# MCU009B_EmuInterface.net
KiCad netlist of a schematic drawn in Altium Designer
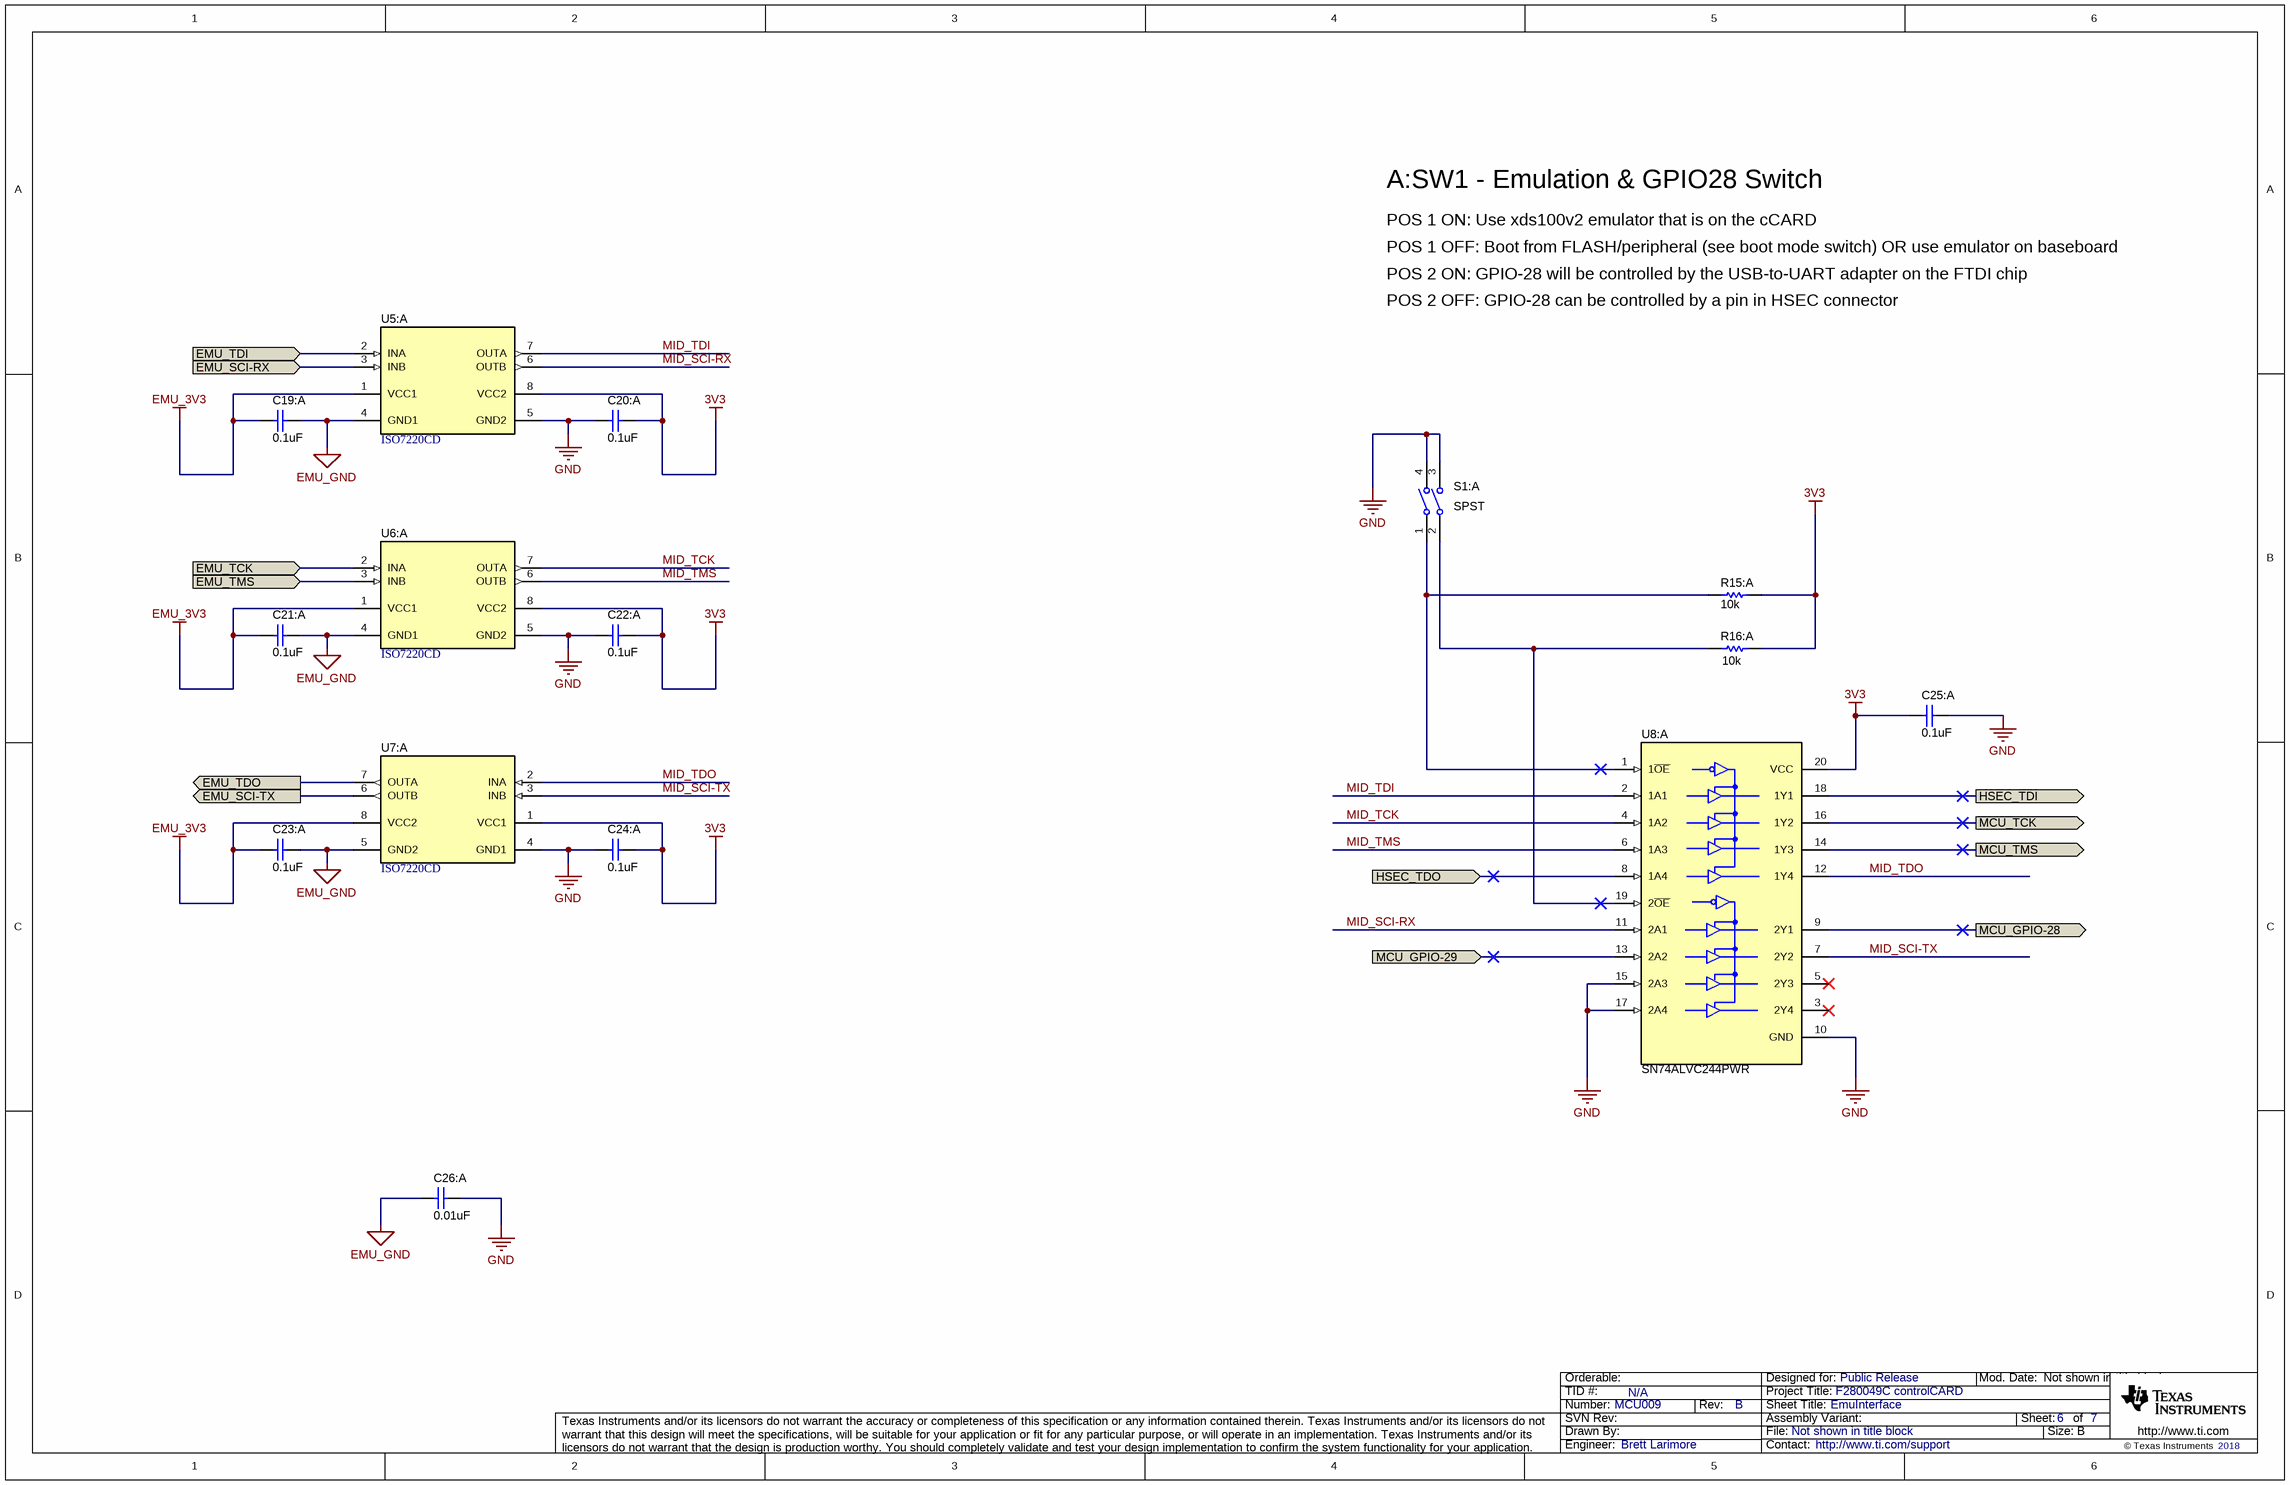
[diagram p0: MCU009B_EmuInterface.SchDoc]

(export (version "E")
  (design (tool "Eeschema 10.0.6"))
  (components
    (comp (ref "C19:A")
      (value "GRM155R71A104KA01D")
      (footprint "0402")
      (description "CAP, CERM, 0.1 uF, 10 V, +/- 10%, X7R, 0402")
      (fields
        (field (name "VALUEDISPLAYED") "0.1uF")
        (field (name "MANUFACTURER") "MuRata")
        (field (name "PUBLISHER") "Texas Instruments")
      )
      (libsource (lib "Altium Vault - TI") (part "Capacitor"))
    )
    (comp (ref "C20:A")
      (value "GRM155R71A104KA01D")
      (footprint "0402")
      (description "CAP, CERM, 0.1 uF, 10 V, +/- 10%, X7R, 0402")
      (fields
        (field (name "VALUEDISPLAYED") "0.1uF")
        (field (name "MANUFACTURER") "MuRata")
        (field (name "PUBLISHER") "Texas Instruments")
      )
      (libsource (lib "Altium Vault - TI") (part "Capacitor"))
    )
    (comp (ref "C21:A")
      (value "GRM155R71A104KA01D")
      (footprint "0402")
      (description "CAP, CERM, 0.1 uF, 10 V, +/- 10%, X7R, 0402")
      (fields
        (field (name "VALUEDISPLAYED") "0.1uF")
        (field (name "MANUFACTURER") "MuRata")
        (field (name "PUBLISHER") "Texas Instruments")
      )
      (libsource (lib "Altium Vault - TI") (part "Capacitor"))
    )
    (comp (ref "C22:A")
      (value "GRM155R71A104KA01D")
      (footprint "0402")
      (description "CAP, CERM, 0.1 uF, 10 V, +/- 10%, X7R, 0402")
      (fields
        (field (name "VALUEDISPLAYED") "0.1uF")
        (field (name "MANUFACTURER") "MuRata")
        (field (name "PUBLISHER") "Texas Instruments")
      )
      (libsource (lib "Altium Vault - TI") (part "Capacitor"))
    )
    (comp (ref "C23:A")
      (value "GRM155R71A104KA01D")
      (footprint "0402")
      (description "CAP, CERM, 0.1 uF, 10 V, +/- 10%, X7R, 0402")
      (fields
        (field (name "VALUEDISPLAYED") "0.1uF")
        (field (name "MANUFACTURER") "MuRata")
        (field (name "PUBLISHER") "Texas Instruments")
      )
      (libsource (lib "Altium Vault - TI") (part "Capacitor"))
    )
    (comp (ref "C24:A")
      (value "GRM155R71A104KA01D")
      (footprint "0402")
      (description "CAP, CERM, 0.1 uF, 10 V, +/- 10%, X7R, 0402")
      (fields
        (field (name "VALUEDISPLAYED") "0.1uF")
        (field (name "MANUFACTURER") "MuRata")
        (field (name "PUBLISHER") "Texas Instruments")
      )
      (libsource (lib "Altium Vault - TI") (part "Capacitor"))
    )
    (comp (ref "C25:A")
      (value "GRM155R71A104KA01D")
      (footprint "0402")
      (description "CAP, CERM, 0.1 uF, 10 V, +/- 10%, X7R, 0402")
      (fields
        (field (name "VALUEDISPLAYED") "0.1uF")
        (field (name "MANUFACTURER") "MuRata")
        (field (name "PUBLISHER") "Texas Instruments")
      )
      (libsource (lib "Altium Vault - TI") (part "Capacitor"))
    )
    (comp (ref "C26:A")
      (value "1812SC103KAT1A")
      (footprint "1812")
      (description "CAP, CERM, 0.01 uF, 1500 V, +/- 10%, X7R, 1812")
      (fields
        (field (name "VALUEDISPLAYED") "0.01uF")
        (field (name "MANUFACTURER") "AVX")
        (field (name "PUBLISHER") "Texas Instruments")
      )
      (libsource (lib "Altium Vault - TI") (part "Capacitor"))
    )
    (comp (ref "R15:A")
      (value "CRCW040210K0JNED")
      (footprint "0402")
      (description "RES, 10 k, 5%, 0.063 W, AEC-Q200 Grade 0, 0402")
      (fields (field (name "VALUEDISPLAYED") "10k") (field (name "MANUFACTURER") "Vishay-Dale"))
      (libsource (lib "Altium Vault - TI") (part "Resistor"))
    )
    (comp (ref "R16:A")
      (value "CRCW040210K0JNED")
      (footprint "0402")
      (description "RES, 10 k, 5%, 0.063 W, AEC-Q200 Grade 0, 0402")
      (fields (field (name "VALUEDISPLAYED") "10k") (field (name "MANUFACTURER") "Vishay-Dale"))
      (libsource (lib "Altium Vault - TI") (part "Resistor"))
    )
    (comp (ref "S1:A")
      (value "218-2LPST")
      (footprint "SW_218-2LP")
      (description "Switch, SPST, 2 Pos, 25mA, 24VDC, SMD")
      (fields
        (field (name "MANUFACTURER") "CTS Electrocomponents")
        (field (name "CIRCUIT") "SPST")
        (field (name "PUBLISHER") "Texas Instruments")
      )
      (libsource (lib "Altium Vault - TI") (part "SW_2SPST"))
    )
    (comp (ref "U5:A")
      (value "ISO7220CD")
      (footprint "D0008B_N")
      (fields (field (name "MANUFACTURER") "Texas Instruments"))
      (libsource (lib "Altium Vault - TI") (part "TI-ISO7220C-SOIC_D-8"))
    )
    (comp (ref "U6:A")
      (value "ISO7220CD")
      (footprint "D0008B_N")
      (fields (field (name "MANUFACTURER") "Texas Instruments"))
      (libsource (lib "Altium Vault - TI") (part "TI-ISO7220C-SOIC_D-8"))
    )
    (comp (ref "U7:A")
      (value "ISO7220CD")
      (footprint "D0008B_N")
      (fields (field (name "MANUFACTURER") "Texas Instruments"))
      (libsource (lib "") (part "TI-ISO7220C-SOIC_D-8_1"))
    )
    (comp (ref "U8:A")
      (value "SN74ALVC244PWR")
      (footprint "PW0020A_N")
      (description "Octal Buffer/Driver With 3-State OUtputs, PW0020A (TSSOP-20)")
      (fields
        (field (name "MANUFACTURER") "Texas Instruments")
        (field (name "GENERIC PART NUMBER") "SN74ALVC244")
      )
      (libsource (lib "Altium Vault - TI") (part "CMP-0047070-3"))
    )
  )
  (nets
    (net (code "1") (name "/EMU_SCI-RX") (class "Default")
      (node (ref "U5:A") (pin "3") (pinfunction "INB_3") (pintype "input"))
    )
    (net (code "2") (name "/EMU_SCI-TX") (class "Default")
      (node (ref "U7:A") (pin "6") (pinfunction "OUTB_6") (pintype "output"))
    )
    (net (code "3") (name "/EMU_TCK") (class "Default")
      (node (ref "U6:A") (pin "2") (pinfunction "INA_2") (pintype "input"))
    )
    (net (code "4") (name "/EMU_TDI") (class "Default")
      (node (ref "U5:A") (pin "2") (pinfunction "INA_2") (pintype "input"))
    )
    (net (code "5") (name "/EMU_TDO") (class "Default")
      (node (ref "U7:A") (pin "7") (pinfunction "OUTA_7") (pintype "output"))
    )
    (net (code "6") (name "/EMU_TMS") (class "Default")
      (node (ref "U6:A") (pin "3") (pinfunction "INB_3") (pintype "input"))
    )
    (net (code "7") (name "/HSEC_TDI") (class "Default")
      (node (ref "U8:A") (pin "18") (pinfunction "1Y1_18") (pintype "tri_state"))
    )
    (net (code "8") (name "/HSEC_TDO") (class "Default")
      (node (ref "U8:A") (pin "8") (pinfunction "1A4_8") (pintype "input"))
    )
    (net (code "9") (name "/MCU_GPIO-28") (class "Default")
      (node (ref "U8:A") (pin "9") (pinfunction "2Y1_9") (pintype "tri_state"))
    )
    (net (code "10") (name "/MCU_GPIO-29") (class "Default")
      (node (ref "U8:A") (pin "13") (pinfunction "2A2_13") (pintype "input"))
    )
    (net (code "11") (name "/MCU_TCK") (class "Default")
      (node (ref "U8:A") (pin "16") (pinfunction "1Y2_16") (pintype "tri_state"))
    )
    (net (code "12") (name "/MCU_TMS") (class "Default")
      (node (ref "U8:A") (pin "14") (pinfunction "1Y3_14") (pintype "tri_state"))
    )
    (net (code "13") (name "/MID_SCI-RX") (class "Default")
      (node (ref "U5:A") (pin "6") (pinfunction "OUTB_6") (pintype "output"))
      (node (ref "U8:A") (pin "11") (pinfunction "2A1_11") (pintype "input"))
    )
    (net (code "14") (name "/MID_SCI-TX") (class "Default")
      (node (ref "U7:A") (pin "3") (pinfunction "INB_3") (pintype "input"))
      (node (ref "U8:A") (pin "7") (pinfunction "2Y2_7") (pintype "tri_state"))
    )
    (net (code "15") (name "/MID_TCK") (class "Default")
      (node (ref "U6:A") (pin "7") (pinfunction "OUTA_7") (pintype "output"))
      (node (ref "U8:A") (pin "4") (pinfunction "1A2_4") (pintype "input"))
    )
    (net (code "16") (name "/MID_TDI") (class "Default")
      (node (ref "U5:A") (pin "7") (pinfunction "OUTA_7") (pintype "output"))
      (node (ref "U8:A") (pin "2") (pinfunction "1A1_2") (pintype "input"))
    )
    (net (code "17") (name "/MID_TDO") (class "Default")
      (node (ref "U7:A") (pin "2") (pinfunction "INA_2") (pintype "input"))
      (node (ref "U8:A") (pin "12") (pinfunction "1Y4_12") (pintype "tri_state"))
    )
    (net (code "18") (name "/MID_TMS") (class "Default")
      (node (ref "U6:A") (pin "6") (pinfunction "OUTB_6") (pintype "output"))
      (node (ref "U8:A") (pin "6") (pinfunction "1A3_6") (pintype "input"))
    )
    (net (code "19") (name "3V3") (class "Default")
      (node (ref "C20:A") (pin "1") (pinfunction "1_1") (pintype "passive"))
      (node (ref "C22:A") (pin "1") (pinfunction "1_1") (pintype "passive"))
      (node (ref "C24:A") (pin "1") (pinfunction "1_1") (pintype "passive"))
      (node (ref "C25:A") (pin "2") (pinfunction "2_2") (pintype "passive"))
      (node (ref "R15:A") (pin "2") (pinfunction "2_2") (pintype "passive"))
      (node (ref "R16:A") (pin "2") (pinfunction "2_2") (pintype "passive"))
      (node (ref "U5:A") (pin "8") (pinfunction "VCC2_8") (pintype "power_in"))
      (node (ref "U6:A") (pin "8") (pinfunction "VCC2_8") (pintype "power_in"))
      (node (ref "U7:A") (pin "1") (pinfunction "VCC1_1") (pintype "power_in"))
      (node (ref "U8:A") (pin "20") (pinfunction "VCC_20") (pintype "power_in"))
    )
    (net (code "20") (name "EMU_3V3") (class "Default")
      (node (ref "C19:A") (pin "2") (pinfunction "2_2") (pintype "passive"))
      (node (ref "C21:A") (pin "2") (pinfunction "2_2") (pintype "passive"))
      (node (ref "C23:A") (pin "2") (pinfunction "2_2") (pintype "passive"))
      (node (ref "U5:A") (pin "1") (pinfunction "VCC1_1") (pintype "power_in"))
      (node (ref "U6:A") (pin "1") (pinfunction "VCC1_1") (pintype "power_in"))
      (node (ref "U7:A") (pin "8") (pinfunction "VCC2_8") (pintype "power_in"))
    )
    (net (code "21") (name "EMU_GND") (class "Default")
      (node (ref "C19:A") (pin "1") (pinfunction "1_1") (pintype "passive"))
      (node (ref "C21:A") (pin "1") (pinfunction "1_1") (pintype "passive"))
      (node (ref "C23:A") (pin "1") (pinfunction "1_1") (pintype "passive"))
      (node (ref "C26:A") (pin "2") (pinfunction "2_2") (pintype "passive"))
      (node (ref "U5:A") (pin "4") (pinfunction "GND1_4") (pintype "power_in"))
      (node (ref "U6:A") (pin "4") (pinfunction "GND1_4") (pintype "power_in"))
      (node (ref "U7:A") (pin "5") (pinfunction "GND2_5") (pintype "power_in"))
    )
    (net (code "22") (name "GND") (class "Default")
      (node (ref "C20:A") (pin "2") (pinfunction "2_2") (pintype "passive"))
      (node (ref "C22:A") (pin "2") (pinfunction "2_2") (pintype "passive"))
      (node (ref "C24:A") (pin "2") (pinfunction "2_2") (pintype "passive"))
      (node (ref "C25:A") (pin "1") (pinfunction "1_1") (pintype "passive"))
      (node (ref "C26:A") (pin "1") (pinfunction "1_1") (pintype "passive"))
      (node (ref "S1:A") (pin "3") (pinfunction "3_3") (pintype "passive"))
      (node (ref "S1:A") (pin "4") (pinfunction "4_4") (pintype "passive"))
      (node (ref "U5:A") (pin "5") (pinfunction "GND2_5") (pintype "power_in"))
      (node (ref "U6:A") (pin "5") (pinfunction "GND2_5") (pintype "power_in"))
      (node (ref "U7:A") (pin "4") (pinfunction "GND1_4") (pintype "power_in"))
      (node (ref "U8:A") (pin "10") (pinfunction "GND_10") (pintype "power_in"))
      (node (ref "U8:A") (pin "15") (pinfunction "2A3_15") (pintype "input"))
      (node (ref "U8:A") (pin "17") (pinfunction "2A4_17") (pintype "input"))
    )
    (net (code "23") (name "Net-(U8:A-1~{OE})") (class "Default")
      (node (ref "R15:A") (pin "1") (pinfunction "1_1") (pintype "passive"))
      (node (ref "S1:A") (pin "1") (pinfunction "1_1") (pintype "passive"))
      (node (ref "U8:A") (pin "1") (pinfunction "1~{OE}_1") (pintype "input"))
    )
    (net (code "24") (name "Net-(U8:A-2~{OE})") (class "Default")
      (node (ref "R16:A") (pin "1") (pinfunction "1_1") (pintype "passive"))
      (node (ref "S1:A") (pin "2") (pinfunction "2_2") (pintype "passive"))
      (node (ref "U8:A") (pin "19") (pinfunction "2~{OE}_19") (pintype "input"))
    )
    (net (code "25") (name "unconnected-(U8:A-2Y3-Pad5)") (class "Default")
      (node (ref "U8:A") (pin "5") (pinfunction "2Y3_5") (pintype "tri_state+no_connect"))
    )
    (net (code "26") (name "unconnected-(U8:A-2Y4-Pad3)") (class "Default")
      (node (ref "U8:A") (pin "3") (pinfunction "2Y4_3") (pintype "tri_state+no_connect"))
    )
  )
)
